# R1250GS_HandHeater_and_rear_5-12V.net
KiCad netlist of a schematic drawn in Altium Designer
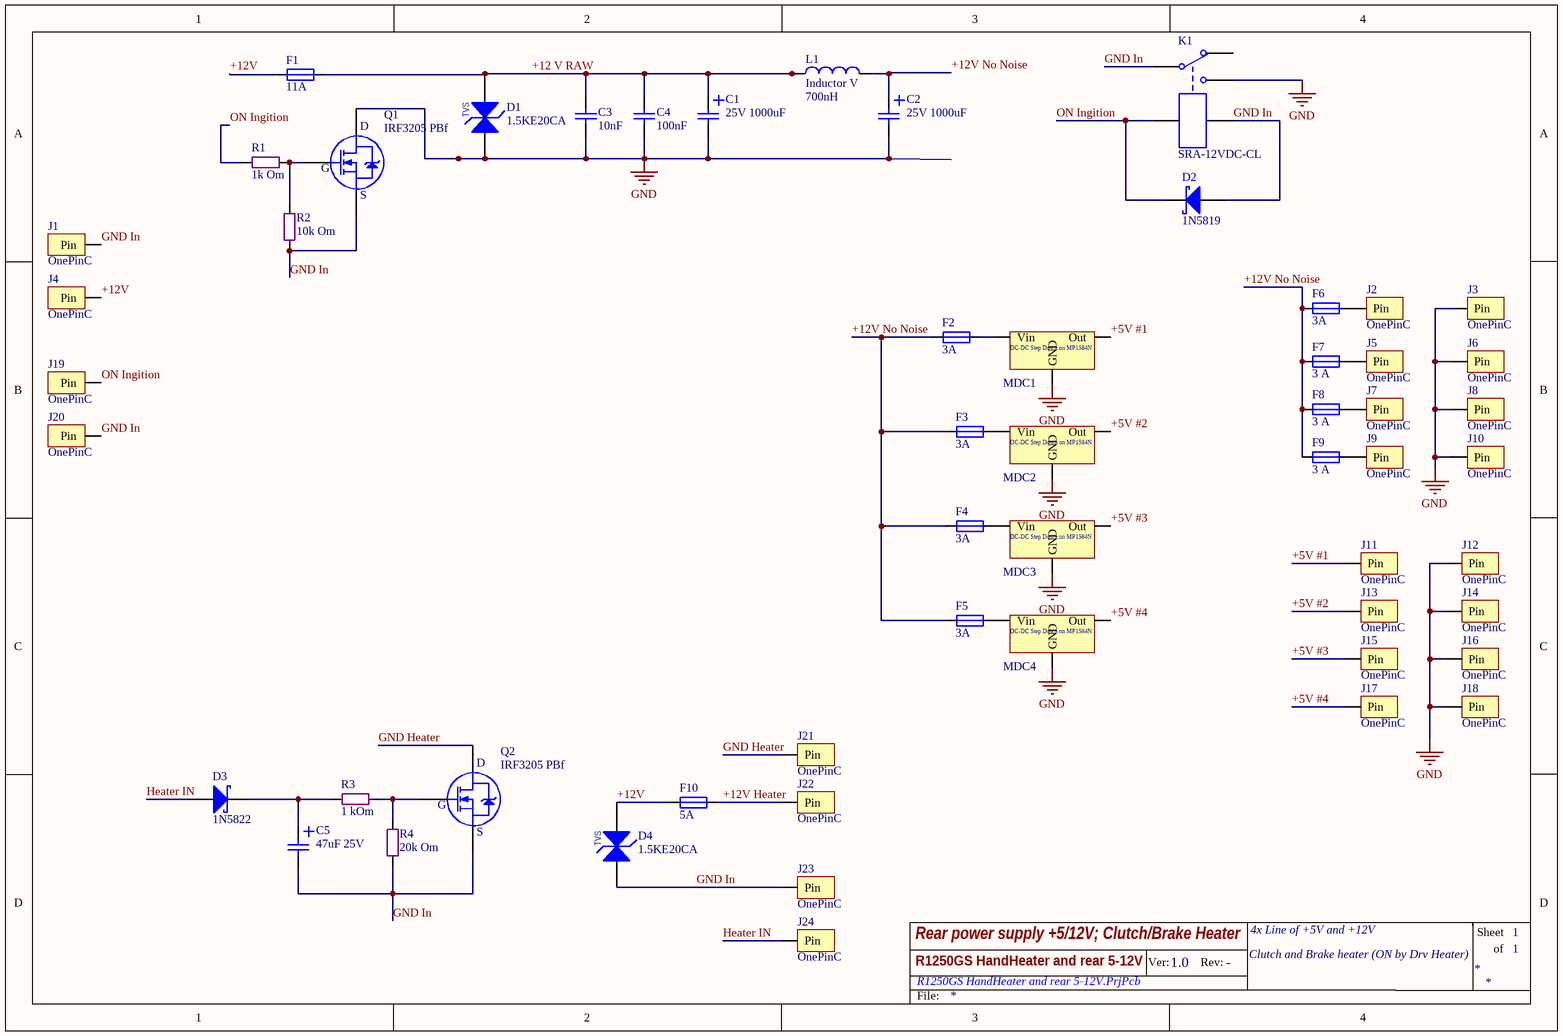
[diagram p0: R1250GS HandHeater and rear 5-12V.SchDoc]

(export (version "E")
  (design (tool "Eeschema 10.0.6"))
  (components
    (comp (ref "C1")
      (value "25V 1000uF")
      (footprint "Capacitor:Cap E p5.08mm D10.2mm (3p)")
      (description "Capacitor")
      (libsource (lib "Capacitor") (part "Cap E 1000mF x 25V"))
    )
    (comp (ref "C2")
      (value "25V 1000uF")
      (footprint "Capacitor:Cap E p5.08mm D10.2mm (3p)")
      (description "Capacitor")
      (libsource (lib "Capacitor") (part "Cap E 1000mF x 25V"))
    )
    (comp (ref "C3")
      (value "10nF")
      (footprint "Capacitor:SMD 1206 (3216)")
      (description "Capacitor")
      (libsource (lib "Capacitor") (part "Cap Ceramic SMD (All)"))
    )
    (comp (ref "C4")
      (value "100nF")
      (footprint "Capacitor:SMD 1206 (3216)")
      (description "Capacitor")
      (libsource (lib "Capacitor") (part "Cap Ceramic SMD (All)"))
    )
    (comp (ref "C5")
      (value "47uF 25V")
      (footprint "Capacitor:Cap E p2mm D6.5xH11")
      (description "Capacitor")
      (libsource (lib "Capacitor") (part "Cap Elecrolitic"))
    )
    (comp (ref "D1")
      (value "1.5KE20CA")
      (footprint "Diodes:TVS diode DO-201 V")
      (description "1500W Transil (TVS Diode)")
      (libsource (lib "Diodes") (part "TVS 1.5KE20CA"))
    )
    (comp (ref "D2")
      (value "1N5819")
      (footprint "Diodes:Diode DO-35")
      (description "Shotki  Diode")
      (libsource (lib "Diodes") (part "D Shotki All"))
    )
    (comp (ref "D3")
      (value "1N5822")
      (footprint "Diodes:Diode DO-41 - Vertical")
      (description "Shotki  Diode")
      (libsource (lib "Diodes") (part "D Shotki All"))
    )
    (comp (ref "D4")
      (value "1.5KE20CA")
      (footprint "Diodes:TVS diode DO-201 V")
      (description "1500W Transil (TVS Diode)")
      (libsource (lib "Diodes") (part "TVS 1.5KE20CA"))
    )
    (comp (ref "F1")
      (value "11A")
      (footprint "PassiveComponents:Fuse RGE1100")
      (description "Round fuse")
      (libsource (lib "PassiveComponents") (part "Fuse"))
    )
    (comp (ref "F2")
      (value "3A")
      (footprint "PassiveComponents:Fuse SM250")
      (description "Round fuse")
      (libsource (lib "PassiveComponents") (part "Fuse"))
    )
    (comp (ref "F3")
      (value "3A")
      (footprint "PassiveComponents:Fuse SM250")
      (description "Round fuse")
      (libsource (lib "PassiveComponents") (part "Fuse"))
    )
    (comp (ref "F4")
      (value "3A")
      (footprint "PassiveComponents:Fuse SM250")
      (description "Round fuse")
      (libsource (lib "PassiveComponents") (part "Fuse"))
    )
    (comp (ref "F5")
      (value "3A")
      (footprint "PassiveComponents:Fuse SM250")
      (description "Round fuse")
      (libsource (lib "PassiveComponents") (part "Fuse"))
    )
    (comp (ref "F6")
      (value "3A")
      (footprint "PassiveComponents:Fuse MF-R300 (3A)")
      (description "Round fuse")
      (libsource (lib "PassiveComponents") (part "Fuse"))
    )
    (comp (ref "F7")
      (value "3 A")
      (footprint "PassiveComponents:Fuse MF-R300 (3A)")
      (description "Round fuse")
      (libsource (lib "PassiveComponents") (part "Fuse"))
    )
    (comp (ref "F8")
      (value "3 A")
      (footprint "PassiveComponents:Fuse MF-R300 (3A)")
      (description "Round fuse")
      (libsource (lib "PassiveComponents") (part "Fuse"))
    )
    (comp (ref "F9")
      (value "3 A")
      (footprint "PassiveComponents:Fuse MF-R300 (3A)")
      (description "Round fuse")
      (libsource (lib "PassiveComponents") (part "Fuse"))
    )
    (comp (ref "F10")
      (value "5A")
      (footprint "PassiveComponents:Fuse MF-R500 (5A)")
      (description "Round fuse")
      (libsource (lib "PassiveComponents") (part "Fuse"))
    )
    (comp (ref "J1")
      (value "OnePinC")
      (footprint "Connector:OnePin 1.8x4 - Square")
      (description "Only pad")
      (libsource (lib "") (part "OnePin Connector_1"))
    )
    (comp (ref "J2")
      (value "OnePinC")
      (footprint "Connector:OnePin 1.2x3 - Rounded")
      (description "Only pad")
      (libsource (lib "Connector") (part "OnePin Connector"))
    )
    (comp (ref "J3")
      (value "OnePinC")
      (footprint "Connector:OnePin 1.2x3 - Square")
      (description "Only pad")
      (libsource (lib "Connector") (part "OnePin Connector"))
    )
    (comp (ref "J4")
      (value "OnePinC")
      (footprint "Connector:OnePin 1.8x4 - Rounded")
      (description "Only pad")
      (libsource (lib "") (part "OnePin Connector_1"))
    )
    (comp (ref "J5")
      (value "OnePinC")
      (footprint "Connector:OnePin 1.2x3 - Rounded")
      (description "Only pad")
      (libsource (lib "Connector") (part "OnePin Connector"))
    )
    (comp (ref "J6")
      (value "OnePinC")
      (footprint "Connector:OnePin 1.2x3 - Square")
      (description "Only pad")
      (libsource (lib "Connector") (part "OnePin Connector"))
    )
    (comp (ref "J7")
      (value "OnePinC")
      (footprint "Connector:OnePin 1.2x3 - Rounded")
      (description "Only pad")
      (libsource (lib "Connector") (part "OnePin Connector"))
    )
    (comp (ref "J8")
      (value "OnePinC")
      (footprint "Connector:OnePin 1.2x3 - Square")
      (description "Only pad")
      (libsource (lib "Connector") (part "OnePin Connector"))
    )
    (comp (ref "J9")
      (value "OnePinC")
      (footprint "Connector:OnePin 1.2x3 - Rounded")
      (description "Only pad")
      (libsource (lib "Connector") (part "OnePin Connector"))
    )
    (comp (ref "J10")
      (value "OnePinC")
      (footprint "Connector:OnePin 1.2x3 - Square")
      (description "Only pad")
      (libsource (lib "Connector") (part "OnePin Connector"))
    )
    (comp (ref "J11")
      (value "OnePinC")
      (footprint "Connector:OnePin 1.2x3 - Rounded")
      (description "Only pad")
      (libsource (lib "Connector") (part "OnePin Connector"))
    )
    (comp (ref "J12")
      (value "OnePinC")
      (footprint "Connector:OnePin 1.2x3 - Square")
      (description "Only pad")
      (libsource (lib "Connector") (part "OnePin Connector"))
    )
    (comp (ref "J13")
      (value "OnePinC")
      (footprint "Connector:OnePin 1.2x3 - Rounded")
      (description "Only pad")
      (libsource (lib "Connector") (part "OnePin Connector"))
    )
    (comp (ref "J14")
      (value "OnePinC")
      (footprint "Connector:OnePin 1.2x3 - Square")
      (description "Only pad")
      (libsource (lib "Connector") (part "OnePin Connector"))
    )
    (comp (ref "J15")
      (value "OnePinC")
      (footprint "Connector:OnePin 1.2x3 - Rounded")
      (description "Only pad")
      (libsource (lib "Connector") (part "OnePin Connector"))
    )
    (comp (ref "J16")
      (value "OnePinC")
      (footprint "Connector:OnePin 1.2x3 - Square")
      (description "Only pad")
      (libsource (lib "Connector") (part "OnePin Connector"))
    )
    (comp (ref "J17")
      (value "OnePinC")
      (footprint "Connector:OnePin 1.2x3 - Rounded")
      (description "Only pad")
      (libsource (lib "Connector") (part "OnePin Connector"))
    )
    (comp (ref "J18")
      (value "OnePinC")
      (footprint "Connector:OnePin 1.2x3 - Square")
      (description "Only pad")
      (libsource (lib "Connector") (part "OnePin Connector"))
    )
    (comp (ref "J19")
      (value "OnePinC")
      (footprint "Connector:OnePin 1.2x3")
      (description "Only pad")
      (libsource (lib "") (part "OnePin Connector_1"))
    )
    (comp (ref "J20")
      (value "OnePinC")
      (footprint "Connector:OnePin 1.2x3 - Square")
      (description "Only pad")
      (libsource (lib "") (part "OnePin Connector_1"))
    )
    (comp (ref "J21")
      (value "OnePinC")
      (footprint "Connector:OnePin 1.8x4 - Square")
      (description "Only pad")
      (libsource (lib "Connector") (part "OnePin Connector"))
    )
    (comp (ref "J22")
      (value "OnePinC")
      (footprint "Connector:OnePin 1.8x4 - Rounded")
      (description "Only pad")
      (libsource (lib "Connector") (part "OnePin Connector"))
    )
    (comp (ref "J23")
      (value "OnePinC")
      (footprint "Connector:OnePin 1.2x3 - Square")
      (description "Only pad")
      (libsource (lib "Connector") (part "OnePin Connector"))
    )
    (comp (ref "J24")
      (value "OnePinC")
      (footprint "Connector:OnePin 1.2x3")
      (description "Only pad")
      (libsource (lib "Connector") (part "OnePin Connector"))
    )
    (comp (ref "K1")
      (value "SRA-12VDC-CL")
      (footprint "Relay:SRA-12VDC-CL")
      (description "Single-Pole Dual-Throw Relay")
      (libsource (lib "Relay") (part "SRA-12VDC-CL"))
    )
    (comp (ref "L1")
      (value "Inductor V")
      (footprint "Transformers:Toroid V D20 W7")
      (description "Inductor Vertical")
      (fields (field (name "ALTIUM_VALUE") "700nH") (field (name "PUBLISHER") "Altium Limited"))
      (libsource (lib "Transformers") (part "Inductor V"))
    )
    (comp (ref "MDC1")
      (value "DC-DC")
      (footprint "Modules:DC-DC_MP1584N (SMALL)")
      (description "DC-DC StepDown")
      (libsource (lib "Modules") (part "DC-DC MP1584N"))
    )
    (comp (ref "MDC2")
      (value "DC-DC")
      (footprint "Modules:DC-DC_MP1584N (SMALL)")
      (description "DC-DC StepDown")
      (libsource (lib "Modules") (part "DC-DC MP1584N"))
    )
    (comp (ref "MDC3")
      (value "DC-DC")
      (footprint "Modules:DC-DC_MP1584N (SMALL)")
      (description "DC-DC StepDown")
      (libsource (lib "Modules") (part "DC-DC MP1584N"))
    )
    (comp (ref "MDC4")
      (value "DC-DC")
      (footprint "Modules:DC-DC_MP1584N (SMALL)")
      (description "DC-DC StepDown")
      (libsource (lib "Modules") (part "DC-DC MP1584N"))
    )
    (comp (ref "Q1")
      (value "IRF3205 PBf")
      (footprint "GeneralCases:TO220-2 HighPower")
      (description "N-Channel 55V - 0.008Ω - 110A")
      (libsource (lib "Transistor") (part "IRF3205"))
    )
    (comp (ref "Q2")
      (value "IRF3205 PBf")
      (footprint "GeneralCases:TO220-2 HighPower")
      (description "N-Channel 55V - 0.008Ω - 110A")
      (libsource (lib "Transistor") (part "IRF3205"))
    )
    (comp (ref "R1")
      (value "1k Om")
      (footprint "PassiveComponents:SMD 0805 (2012)")
      (libsource (lib "PassiveComponents") (part "Res All Types"))
    )
    (comp (ref "R2")
      (value "10k Om")
      (footprint "PassiveComponents:SMD 0805 (2012)")
      (libsource (lib "PassiveComponents") (part "Res All Types"))
    )
    (comp (ref "R3")
      (value "1 kOm")
      (footprint "PassiveComponents:SMD 0805 (2012)")
      (libsource (lib "PassiveComponents") (part "Res All Types"))
    )
    (comp (ref "R4")
      (value "20k Om")
      (footprint "PassiveComponents:SMD 0805 (2012)")
      (libsource (lib "PassiveComponents") (part "Res All Types"))
    )
  )
  (nets
    (net (code "1") (name "/+5V #1") (class "Default")
      (node (ref "J11") (pin "1") (pinfunction "Pin_1") (pintype "passive"))
      (node (ref "MDC1") (pin "OUT") (pinfunction "Out_OUT") (pintype "passive"))
    )
    (net (code "2") (name "/+5V #2") (class "Default")
      (node (ref "J13") (pin "1") (pinfunction "Pin_1") (pintype "passive"))
      (node (ref "MDC2") (pin "OUT") (pinfunction "Out_OUT") (pintype "passive"))
    )
    (net (code "3") (name "/+5V #3") (class "Default")
      (node (ref "J15") (pin "1") (pinfunction "Pin_1") (pintype "passive"))
      (node (ref "MDC3") (pin "OUT") (pinfunction "Out_OUT") (pintype "passive"))
    )
    (net (code "4") (name "/+5V #4") (class "Default")
      (node (ref "J17") (pin "1") (pinfunction "Pin_1") (pintype "passive"))
      (node (ref "MDC4") (pin "OUT") (pinfunction "Out_OUT") (pintype "passive"))
    )
    (net (code "5") (name "/+12 V RAW") (class "Default")
      (node (ref "C1") (pin "1") (pinfunction "1_1") (pintype "passive"))
      (node (ref "C3") (pin "1") (pinfunction "1_1") (pintype "passive"))
      (node (ref "C4") (pin "1") (pinfunction "1_1") (pintype "passive"))
      (node (ref "D1") (pin "2") (pinfunction "2_2") (pintype "passive"))
      (node (ref "F1") (pin "2") (pinfunction "2_2") (pintype "passive"))
      (node (ref "L1") (pin "1") (pinfunction "1_1") (pintype "passive"))
    )
    (net (code "6") (name "/+12V") (class "Default")
      (node (ref "D4") (pin "2") (pinfunction "2_2") (pintype "passive"))
      (node (ref "F1") (pin "1") (pinfunction "1_1") (pintype "passive"))
      (node (ref "F10") (pin "1") (pinfunction "1_1") (pintype "passive"))
      (node (ref "J4") (pin "1") (pinfunction "Pin_1") (pintype "passive"))
    )
    (net (code "7") (name "/+12V Heater") (class "Default")
      (node (ref "F10") (pin "2") (pinfunction "2_2") (pintype "passive"))
      (node (ref "J22") (pin "1") (pinfunction "Pin_1") (pintype "passive"))
    )
    (net (code "8") (name "/+12V No Noise") (class "Default")
      (node (ref "C2") (pin "1") (pinfunction "1_1") (pintype "passive"))
      (node (ref "F2") (pin "2") (pinfunction "2_2") (pintype "passive"))
      (node (ref "F3") (pin "2") (pinfunction "2_2") (pintype "passive"))
      (node (ref "F4") (pin "2") (pinfunction "2_2") (pintype "passive"))
      (node (ref "F5") (pin "2") (pinfunction "2_2") (pintype "passive"))
      (node (ref "F6") (pin "2") (pinfunction "2_2") (pintype "passive"))
      (node (ref "F7") (pin "2") (pinfunction "2_2") (pintype "passive"))
      (node (ref "F8") (pin "2") (pinfunction "2_2") (pintype "passive"))
      (node (ref "F9") (pin "2") (pinfunction "2_2") (pintype "passive"))
      (node (ref "L1") (pin "2") (pinfunction "2_2") (pintype "passive"))
    )
    (net (code "9") (name "/GND Heater") (class "Default")
      (node (ref "J21") (pin "1") (pinfunction "Pin_1") (pintype "passive"))
      (node (ref "Q2") (pin "2") (pinfunction "D_2") (pintype "passive"))
    )
    (net (code "10") (name "/GND In") (class "Default")
      (node (ref "C5") (pin "2") (pinfunction "2_2") (pintype "passive"))
      (node (ref "D2") (pin "A") (pinfunction "A_A") (pintype "passive"))
      (node (ref "D4") (pin "1") (pinfunction "1_1") (pintype "passive"))
      (node (ref "J1") (pin "1") (pinfunction "Pin_1") (pintype "passive"))
      (node (ref "J20") (pin "1") (pinfunction "Pin_1") (pintype "passive"))
      (node (ref "J23") (pin "1") (pinfunction "Pin_1") (pintype "passive"))
      (node (ref "K1") (pin "2") (pinfunction "2_2") (pintype "passive"))
      (node (ref "K1") (pin "5") (pinfunction "5_5") (pintype "passive"))
      (node (ref "Q1") (pin "3") (pinfunction "S_3") (pintype "passive"))
      (node (ref "Q2") (pin "3") (pinfunction "S_3") (pintype "passive"))
      (node (ref "R2") (pin "1") (pinfunction "1_1") (pintype "passive"))
      (node (ref "R4") (pin "1") (pinfunction "1_1") (pintype "passive"))
    )
    (net (code "11") (name "/Heater IN") (class "Default")
      (node (ref "D3") (pin "A") (pinfunction "A_A") (pintype "passive"))
      (node (ref "J24") (pin "1") (pinfunction "Pin_1") (pintype "passive"))
    )
    (net (code "12") (name "/ON Ingition") (class "Default")
      (node (ref "D2") (pin "K") (pinfunction "K_K") (pintype "passive"))
      (node (ref "J19") (pin "1") (pinfunction "Pin_1") (pintype "passive"))
      (node (ref "K1") (pin "4") (pinfunction "4_4") (pintype "passive"))
      (node (ref "R1") (pin "1") (pinfunction "1_1") (pintype "passive"))
    )
    (net (code "13") (name "GND") (class "Default")
      (node (ref "C1") (pin "2") (pinfunction "2_2") (pintype "passive"))
      (node (ref "C2") (pin "2") (pinfunction "2_2") (pintype "passive"))
      (node (ref "C3") (pin "2") (pinfunction "2_2") (pintype "passive"))
      (node (ref "C4") (pin "2") (pinfunction "2_2") (pintype "passive"))
      (node (ref "D1") (pin "1") (pinfunction "1_1") (pintype "passive"))
      (node (ref "J10") (pin "1") (pinfunction "Pin_1") (pintype "passive"))
      (node (ref "J12") (pin "1") (pinfunction "Pin_1") (pintype "passive"))
      (node (ref "J14") (pin "1") (pinfunction "Pin_1") (pintype "passive"))
      (node (ref "J16") (pin "1") (pinfunction "Pin_1") (pintype "passive"))
      (node (ref "J18") (pin "1") (pinfunction "Pin_1") (pintype "passive"))
      (node (ref "J3") (pin "1") (pinfunction "Pin_1") (pintype "passive"))
      (node (ref "J6") (pin "1") (pinfunction "Pin_1") (pintype "passive"))
      (node (ref "J8") (pin "1") (pinfunction "Pin_1") (pintype "passive"))
      (node (ref "K1") (pin "3") (pinfunction "3_3") (pintype "passive"))
      (node (ref "MDC1") (pin "GND") (pinfunction "GND_GND") (pintype "passive"))
      (node (ref "MDC2") (pin "GND") (pinfunction "GND_GND") (pintype "passive"))
      (node (ref "MDC3") (pin "GND") (pinfunction "GND_GND") (pintype "passive"))
      (node (ref "MDC4") (pin "GND") (pinfunction "GND_GND") (pintype "passive"))
      (node (ref "Q1") (pin "2") (pinfunction "D_2") (pintype "passive"))
    )
    (net (code "14") (name "Net-(C5-Pad1)") (class "Default")
      (node (ref "C5") (pin "1") (pinfunction "1_1") (pintype "passive"))
      (node (ref "D3") (pin "K") (pinfunction "K_K") (pintype "passive"))
      (node (ref "R3") (pin "1") (pinfunction "1_1") (pintype "passive"))
    )
    (net (code "15") (name "Net-(J2-Pin)") (class "Default")
      (node (ref "F6") (pin "1") (pinfunction "1_1") (pintype "passive"))
      (node (ref "J2") (pin "1") (pinfunction "Pin_1") (pintype "passive"))
    )
    (net (code "16") (name "Net-(J5-Pin)") (class "Default")
      (node (ref "F7") (pin "1") (pinfunction "1_1") (pintype "passive"))
      (node (ref "J5") (pin "1") (pinfunction "Pin_1") (pintype "passive"))
    )
    (net (code "17") (name "Net-(J7-Pin)") (class "Default")
      (node (ref "F8") (pin "1") (pinfunction "1_1") (pintype "passive"))
      (node (ref "J7") (pin "1") (pinfunction "Pin_1") (pintype "passive"))
    )
    (net (code "18") (name "Net-(J9-Pin)") (class "Default")
      (node (ref "F9") (pin "1") (pinfunction "1_1") (pintype "passive"))
      (node (ref "J9") (pin "1") (pinfunction "Pin_1") (pintype "passive"))
    )
    (net (code "19") (name "Net-(MDC1-Vin)") (class "Default")
      (node (ref "F2") (pin "1") (pinfunction "1_1") (pintype "passive"))
      (node (ref "MDC1") (pin "IN") (pinfunction "Vin_IN") (pintype "passive"))
    )
    (net (code "20") (name "Net-(MDC2-Vin)") (class "Default")
      (node (ref "F3") (pin "1") (pinfunction "1_1") (pintype "passive"))
      (node (ref "MDC2") (pin "IN") (pinfunction "Vin_IN") (pintype "passive"))
    )
    (net (code "21") (name "Net-(MDC3-Vin)") (class "Default")
      (node (ref "F4") (pin "1") (pinfunction "1_1") (pintype "passive"))
      (node (ref "MDC3") (pin "IN") (pinfunction "Vin_IN") (pintype "passive"))
    )
    (net (code "22") (name "Net-(MDC4-Vin)") (class "Default")
      (node (ref "F5") (pin "1") (pinfunction "1_1") (pintype "passive"))
      (node (ref "MDC4") (pin "IN") (pinfunction "Vin_IN") (pintype "passive"))
    )
    (net (code "23") (name "Net-(Q1-G)") (class "Default")
      (node (ref "Q1") (pin "1") (pinfunction "G_1") (pintype "passive"))
      (node (ref "R1") (pin "2") (pinfunction "2_2") (pintype "passive"))
      (node (ref "R2") (pin "2") (pinfunction "2_2") (pintype "passive"))
    )
    (net (code "24") (name "Net-(Q2-G)") (class "Default")
      (node (ref "Q2") (pin "1") (pinfunction "G_1") (pintype "passive"))
      (node (ref "R3") (pin "2") (pinfunction "2_2") (pintype "passive"))
      (node (ref "R4") (pin "2") (pinfunction "2_2") (pintype "passive"))
    )
    (net (code "25") (name "unconnected-(K1-Pad1)") (class "Default")
      (node (ref "K1") (pin "1") (pinfunction "1_1") (pintype "passive"))
    )
  )
)
